# fancontroller.net
KiCad netlist of a schematic drawn in EAGLE
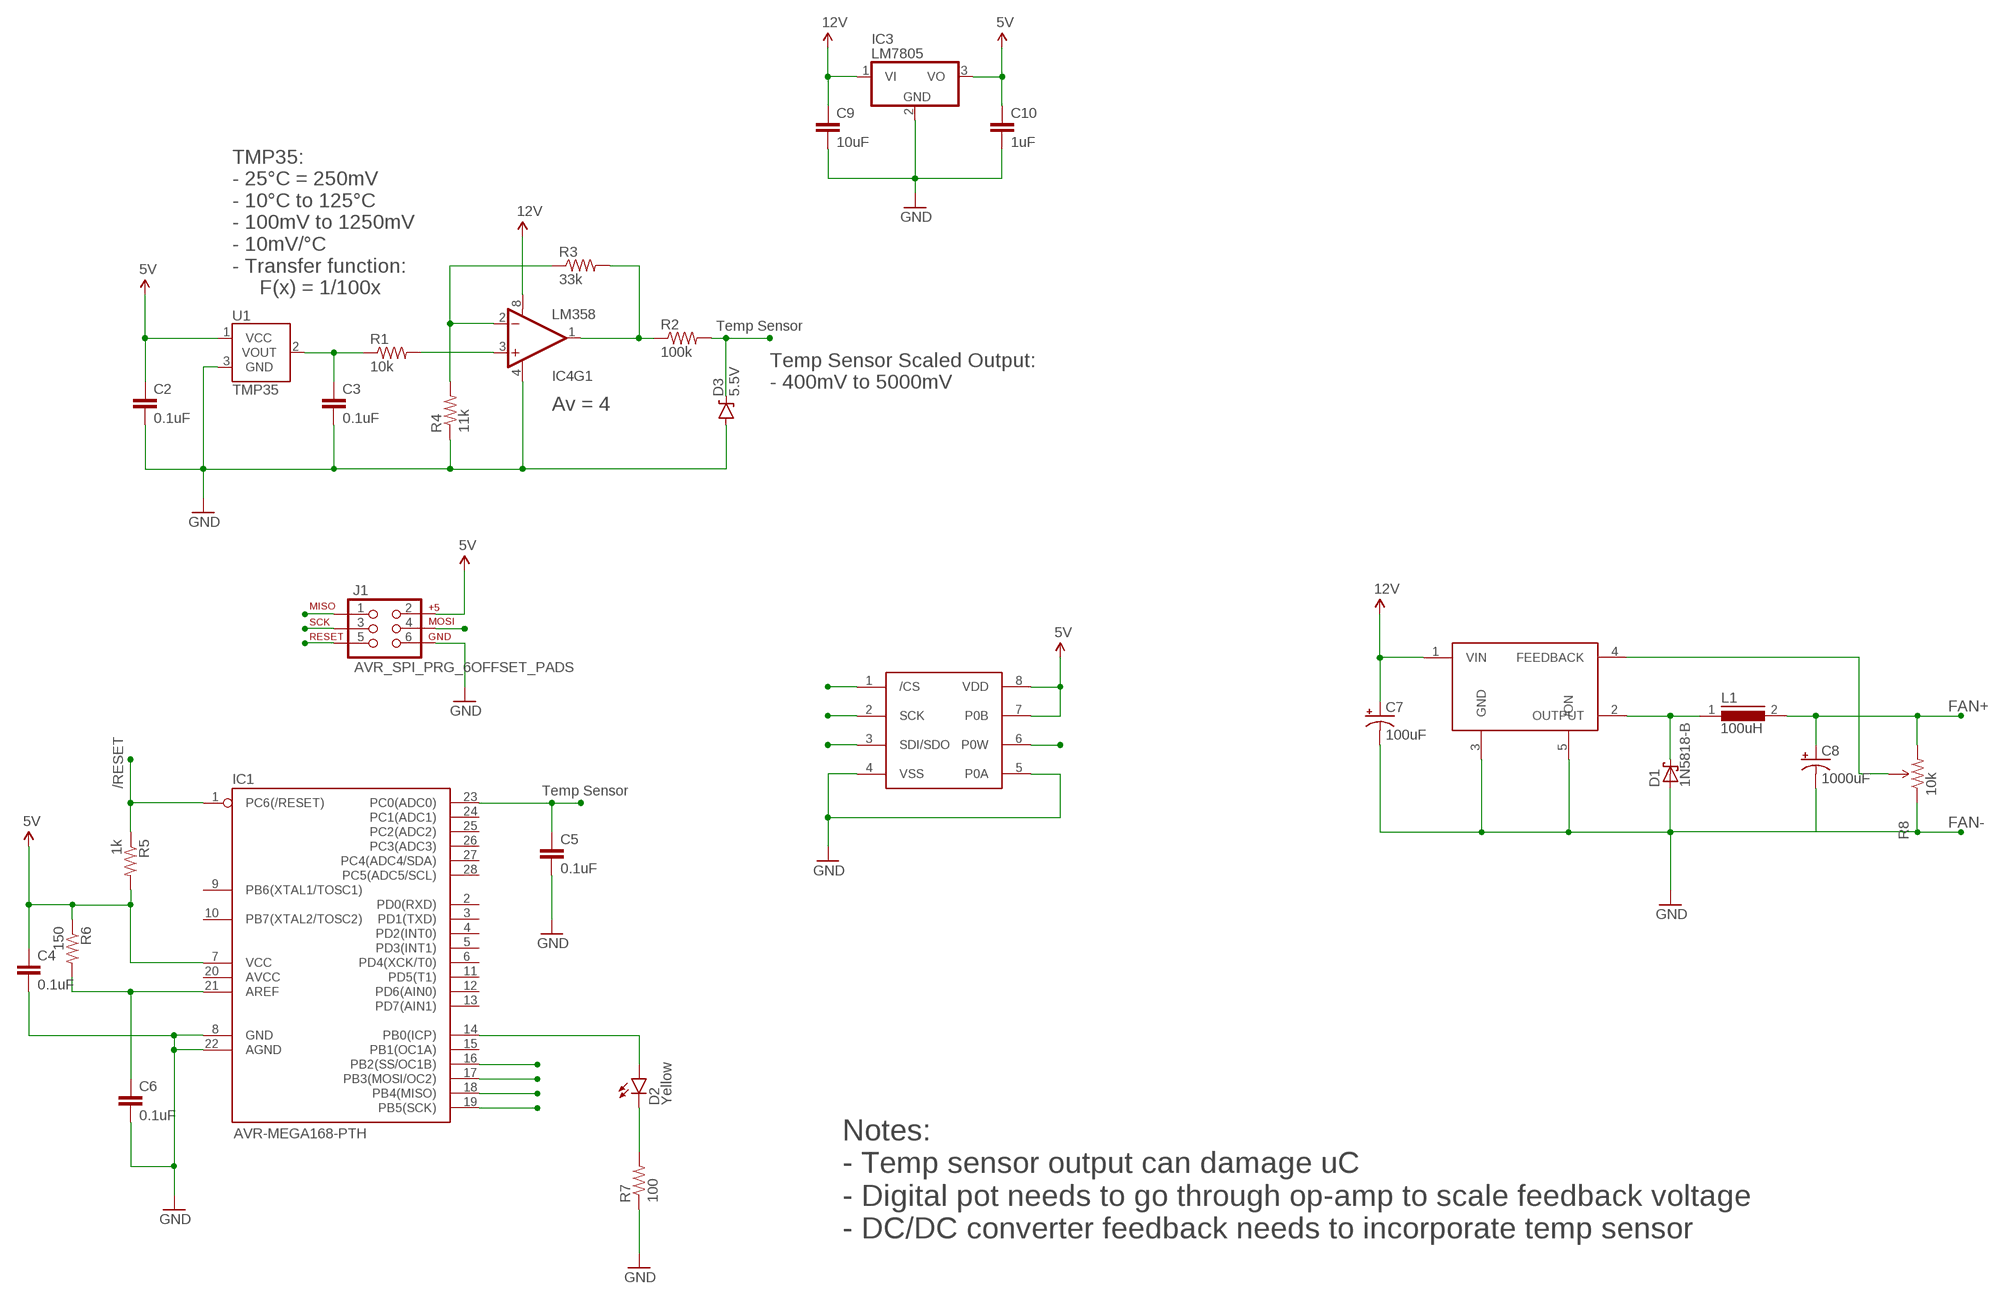
[diagram p0: schematic, sheet 1]

(export (version "E")
  (design (tool "Eeschema 10.0.6"))
  (components
    (comp (ref "C2")
      (value "0.1uF")
      (footprint "eagle-import:CAP-PTH-SMALL")
      (libsource (lib "eagle-import") (part "CAPPTH"))
    )
    (comp (ref "C3")
      (value "0.1uF")
      (footprint "eagle-import:CAP-PTH-SMALL")
      (libsource (lib "eagle-import") (part "CAPPTH"))
    )
    (comp (ref "C4")
      (value "0.1uF")
      (footprint "eagle-import:CAP-PTH-SMALL")
      (libsource (lib "eagle-import") (part "CAPPTH"))
    )
    (comp (ref "C5")
      (value "0.1uF")
      (footprint "eagle-import:CAP-PTH-SMALL")
      (libsource (lib "eagle-import") (part "CAPPTH"))
    )
    (comp (ref "C6")
      (value "0.1uF")
      (footprint "eagle-import:CAP-PTH-SMALL")
      (libsource (lib "eagle-import") (part "CAPPTH"))
    )
    (comp (ref "C7")
      (value "100uF")
      (footprint "eagle-import:CPOL-RADIAL-100UF-25V")
      (libsource (lib "eagle-import") (part "CAP_POLPTH1"))
    )
    (comp (ref "C8")
      (value "1000uF")
      (footprint "eagle-import:CPOL-RADIAL-100UF-25V")
      (libsource (lib "eagle-import") (part "CAP_POLPTH1"))
    )
    (comp (ref "C9")
      (value "10uF")
      (footprint "eagle-import:CAP-PTH-SMALL")
      (libsource (lib "eagle-import") (part "CAPPTH"))
    )
    (comp (ref "C10")
      (value "1uF")
      (footprint "eagle-import:CAP-PTH-SMALL")
      (libsource (lib "eagle-import") (part "CAPPTH"))
    )
    (comp (ref "D1")
      (value "1N5818-B")
      (footprint "eagle-import:DO41-7.6")
      (libsource (lib "eagle-import") (part "1N5818-B"))
    )
    (comp (ref "D2")
      (value "Yellow")
      (footprint "eagle-import:LED5MM")
      (libsource (lib "eagle-import") (part "LED5MM"))
    )
    (comp (ref "D3")
      (value "5.5V")
      (footprint "eagle-import:DIODE-ZENER")
      (libsource (lib "eagle-import") (part "DIODE-ZENERPTH"))
    )
    (comp (ref "IC1")
      (value "AVR-MEGA168-PTH")
      (footprint "eagle-import:DIL28-3")
      (libsource (lib "eagle-import") (part "AVR-MEGA8-PPTH"))
    )
    (comp (ref "IC3")
      (value "LM7805")
      (footprint "eagle-import:TO220V")
      (libsource (lib "eagle-import") (part "78TV12"))
    )
    (comp (ref "IC4")
      (value "LM358")
      (footprint "eagle-import:DIP08-KIT")
      (libsource (lib "eagle-import") (part "LM358KIT"))
    )
    (comp (ref "J1")
      (value "AVR_SPI_PRG_6OFFSET_PADS")
      (footprint "eagle-import:2X3_OFFSET")
      (libsource (lib "eagle-import") (part "AVR_SPI_PRG_6OFFSET_PADS"))
    )
    (comp (ref "L1")
      (value "100uH")
      (footprint "eagle-import:A26GFC")
      (libsource (lib "eagle-import") (part "A26GFC"))
    )
    (comp (ref "R1")
      (value "10k")
      (footprint "eagle-import:AXIAL-0.1")
      (libsource (lib "eagle-import") (part "10KOHM-1/4W-1%(PTH)VERT"))
    )
    (comp (ref "R2")
      (value "100k")
      (footprint "eagle-import:AXIAL-0.1")
      (libsource (lib "eagle-import") (part "10KOHM-1/4W-1%(PTH)VERT"))
    )
    (comp (ref "R3")
      (value "33k")
      (footprint "eagle-import:AXIAL-0.1")
      (libsource (lib "eagle-import") (part "10KOHM-1/4W-1%(PTH)VERT"))
    )
    (comp (ref "R4")
      (value "11k")
      (footprint "eagle-import:AXIAL-0.1")
      (libsource (lib "eagle-import") (part "10KOHM-1/4W-1%(PTH)VERT"))
    )
    (comp (ref "R5")
      (value "1k")
      (footprint "eagle-import:AXIAL-0.1")
      (libsource (lib "eagle-import") (part "10KOHM-1/4W-1%(PTH)VERT"))
    )
    (comp (ref "R6")
      (value "150")
      (footprint "eagle-import:AXIAL-0.1")
      (libsource (lib "eagle-import") (part "10KOHM-1/4W-1%(PTH)VERT"))
    )
    (comp (ref "R7")
      (value "100")
      (footprint "eagle-import:AXIAL-0.1")
      (libsource (lib "eagle-import") (part "10KOHM-1/4W-1%(PTH)VERT"))
    )
    (comp (ref "R8")
      (value "10k")
      (footprint "eagle-import:TRIM_POT_PTH")
      (libsource (lib "eagle-import") (part "TRIMPOTPTH"))
    )
    (comp (ref "U$1")
      (value "LM2576XXVERTICAL")
      (footprint "eagle-import:TO-220-5")
      (libsource (lib "eagle-import") (part "LM2576XXVERTICAL"))
    )
    (comp (ref "U$3")
      (value "MCP4131-103")
      (footprint "eagle-import:PDIP-8")
      (libsource (lib "eagle-import") (part "MCP41X1"))
    )
    (comp (ref "U1")
      (value "TMP35")
      (footprint "eagle-import:TO-92")
      (libsource (lib "eagle-import") (part "TMP36GT9"))
    )
  )
  (nets
    (net (code "1") (name "/MISO") (class "Default")
      (node (ref "IC1") (pin "18") (pinfunction "PB4(MISO)_18") (pintype "bidirectional"))
      (node (ref "J1") (pin "1") (pinfunction "1_1") (pintype "passive"))
    )
    (net (code "2") (name "/MOSI") (class "Default")
      (node (ref "IC1") (pin "17") (pinfunction "PB3(MOSI/OC2)_17") (pintype "bidirectional"))
      (node (ref "J1") (pin "4") (pinfunction "4_4") (pintype "passive"))
      (node (ref "U$3") (pin "3") (pinfunction "SDI/SDO_3") (pintype "bidirectional"))
    )
    (net (code "3") (name "/SCK") (class "Default")
      (node (ref "IC1") (pin "19") (pinfunction "PB5(SCK)_19") (pintype "bidirectional"))
      (node (ref "J1") (pin "3") (pinfunction "3_3") (pintype "passive"))
      (node (ref "U$3") (pin "2") (pinfunction "SCK_2") (pintype "bidirectional"))
    )
    (net (code "4") (name "/TEMP_SENSOR") (class "Default")
      (node (ref "C5") (pin "1") (pinfunction "1_1") (pintype "passive"))
      (node (ref "D3") (pin "P$1") (pinfunction "C_P$1") (pintype "passive"))
      (node (ref "IC1") (pin "23") (pinfunction "PC0(ADC0)_23") (pintype "bidirectional"))
      (node (ref "R2") (pin "P$2") (pinfunction "2_P$2") (pintype "passive"))
    )
    (net (code "5") (name "/{slash}RESET") (class "Default")
      (node (ref "IC1") (pin "1") (pinfunction "PC6(/RESET)_1") (pintype "bidirectional"))
      (node (ref "J1") (pin "5") (pinfunction "5_5") (pintype "passive"))
      (node (ref "R5") (pin "P$1") (pinfunction "1_P$1") (pintype "passive"))
    )
    (net (code "6") (name "/{slash}SS") (class "Default")
      (node (ref "IC1") (pin "16") (pinfunction "PB2(SS/OC1B)_16") (pintype "bidirectional"))
      (node (ref "U$3") (pin "1") (pinfunction "/CS_1") (pintype "bidirectional"))
    )
    (net (code "7") (name "5V") (class "Default")
      (node (ref "C10") (pin "1") (pinfunction "1_1") (pintype "passive"))
      (node (ref "C2") (pin "1") (pinfunction "1_1") (pintype "passive"))
      (node (ref "C4") (pin "1") (pinfunction "1_1") (pintype "passive"))
      (node (ref "IC1") (pin "7") (pinfunction "VCC_7") (pintype "bidirectional"))
      (node (ref "IC3") (pin "3") (pinfunction "VO_3") (pintype "passive"))
      (node (ref "J1") (pin "2") (pinfunction "2_2") (pintype "passive"))
      (node (ref "R5") (pin "P$2") (pinfunction "2_P$2") (pintype "passive"))
      (node (ref "R6") (pin "P$1") (pinfunction "1_P$1") (pintype "passive"))
      (node (ref "U$3") (pin "7") (pinfunction "P0B_7") (pintype "bidirectional"))
      (node (ref "U$3") (pin "8") (pinfunction "VDD_8") (pintype "bidirectional"))
      (node (ref "U1") (pin "1") (pinfunction "VCC_1") (pintype "bidirectional"))
    )
    (net (code "8") (name "12V") (class "Default")
      (node (ref "C7") (pin "1") (pinfunction "+_1") (pintype "passive"))
      (node (ref "C9") (pin "1") (pinfunction "1_1") (pintype "passive"))
      (node (ref "IC3") (pin "1") (pinfunction "VI_1") (pintype "input"))
      (node (ref "IC4") (pin "8") (pinfunction "V+_8") (pintype "power_in"))
      (node (ref "U$1") (pin "1") (pinfunction "VIN_1") (pintype "bidirectional"))
    )
    (net (code "9") (name "GND") (class "Default")
      (node (ref "C10") (pin "2") (pinfunction "2_2") (pintype "passive"))
      (node (ref "C2") (pin "2") (pinfunction "2_2") (pintype "passive"))
      (node (ref "C3") (pin "2") (pinfunction "2_2") (pintype "passive"))
      (node (ref "C4") (pin "2") (pinfunction "2_2") (pintype "passive"))
      (node (ref "C5") (pin "2") (pinfunction "2_2") (pintype "passive"))
      (node (ref "C6") (pin "2") (pinfunction "2_2") (pintype "passive"))
      (node (ref "C7") (pin "2") (pinfunction "-_2") (pintype "passive"))
      (node (ref "C8") (pin "2") (pinfunction "-_2") (pintype "passive"))
      (node (ref "C9") (pin "2") (pinfunction "2_2") (pintype "passive"))
      (node (ref "D1") (pin "A") (pinfunction "A_A") (pintype "passive"))
      (node (ref "D3") (pin "P$2") (pinfunction "A_P$2") (pintype "passive"))
      (node (ref "IC1") (pin "22") (pinfunction "AGND_22") (pintype "bidirectional"))
      (node (ref "IC1") (pin "8") (pinfunction "GND_8") (pintype "bidirectional"))
      (node (ref "IC3") (pin "2") (pinfunction "GND_2") (pintype "passive"))
      (node (ref "IC4") (pin "4") (pinfunction "V-_4") (pintype "power_in"))
      (node (ref "J1") (pin "6") (pinfunction "6_6") (pintype "passive"))
      (node (ref "R4") (pin "P$1") (pinfunction "1_P$1") (pintype "passive"))
      (node (ref "R7") (pin "P$1") (pinfunction "1_P$1") (pintype "passive"))
      (node (ref "R8") (pin "1") (pinfunction "CCW_1") (pintype "passive"))
      (node (ref "U$1") (pin "3") (pinfunction "GND_3") (pintype "bidirectional"))
      (node (ref "U$1") (pin "5") (pinfunction "/ON_5") (pintype "bidirectional"))
      (node (ref "U$3") (pin "4") (pinfunction "VSS_4") (pintype "bidirectional"))
      (node (ref "U$3") (pin "5") (pinfunction "P0A_5") (pintype "bidirectional"))
      (node (ref "U1") (pin "3") (pinfunction "GND_3") (pintype "bidirectional"))
    )
    (net (code "10") (name "Net-(C8-+)") (class "Default")
      (node (ref "C8") (pin "1") (pinfunction "+_1") (pintype "passive"))
      (node (ref "L1") (pin "2") (pinfunction "2_2") (pintype "passive"))
      (node (ref "R8") (pin "3") (pinfunction "CW_3") (pintype "passive"))
    )
    (net (code "11") (name "Net-(D2-C)") (class "Default")
      (node (ref "D2") (pin "K") (pinfunction "C_K") (pintype "passive"))
      (node (ref "R7") (pin "P$2") (pinfunction "2_P$2") (pintype "passive"))
    )
    (net (code "12") (name "Net-(IC1-AREF)") (class "Default")
      (node (ref "C6") (pin "1") (pinfunction "1_1") (pintype "passive"))
      (node (ref "IC1") (pin "21") (pinfunction "AREF_21") (pintype "bidirectional"))
      (node (ref "R6") (pin "P$2") (pinfunction "2_P$2") (pintype "passive"))
    )
    (net (code "13") (name "Net-(IC1-PB0(ICP))") (class "Default")
      (node (ref "D2") (pin "A") (pinfunction "A_A") (pintype "passive"))
      (node (ref "IC1") (pin "14") (pinfunction "PB0(ICP)_14") (pintype "bidirectional"))
    )
    (net (code "14") (name "Net-(IC4A-+IN)") (class "Default")
      (node (ref "IC4") (pin "3") (pinfunction "+IN_3") (pintype "input"))
      (node (ref "R1") (pin "P$2") (pinfunction "2_P$2") (pintype "passive"))
    )
    (net (code "15") (name "Net-(IC4A--IN)") (class "Default")
      (node (ref "IC4") (pin "2") (pinfunction "-IN_2") (pintype "input"))
      (node (ref "R3") (pin "P$1") (pinfunction "1_P$1") (pintype "passive"))
      (node (ref "R4") (pin "P$2") (pinfunction "2_P$2") (pintype "passive"))
    )
    (net (code "16") (name "Net-(IC4A-OUT)") (class "Default")
      (node (ref "IC4") (pin "1") (pinfunction "OUT_1") (pintype "output"))
      (node (ref "R2") (pin "P$1") (pinfunction "1_P$1") (pintype "passive"))
      (node (ref "R3") (pin "P$2") (pinfunction "2_P$2") (pintype "passive"))
    )
    (net (code "17") (name "Net-(R1-1)") (class "Default")
      (node (ref "C3") (pin "1") (pinfunction "1_1") (pintype "passive"))
      (node (ref "R1") (pin "P$1") (pinfunction "1_P$1") (pintype "passive"))
      (node (ref "U1") (pin "2") (pinfunction "VOUT_2") (pintype "bidirectional"))
    )
    (net (code "18") (name "Net-(R8-WIPER)") (class "Default")
      (node (ref "R8") (pin "2") (pinfunction "WIPER_2") (pintype "passive"))
      (node (ref "U$1") (pin "4") (pinfunction "FEEDBACK_4") (pintype "bidirectional"))
    )
    (net (code "19") (name "Net-(U$1-OUTPUT)") (class "Default")
      (node (ref "D1") (pin "C") (pinfunction "C_C") (pintype "passive"))
      (node (ref "L1") (pin "1") (pinfunction "1_1") (pintype "passive"))
      (node (ref "U$1") (pin "2") (pinfunction "OUTPUT_2") (pintype "bidirectional"))
    )
    (net (code "20") (name "unconnected-(IC1-AVCC-Pad20)") (class "Default")
      (node (ref "IC1") (pin "20") (pinfunction "AVCC_20") (pintype "bidirectional"))
    )
    (net (code "21") (name "unconnected-(IC1-PB1(OC1A)-Pad15)") (class "Default")
      (node (ref "IC1") (pin "15") (pinfunction "PB1(OC1A)_15") (pintype "bidirectional"))
    )
    (net (code "22") (name "unconnected-(IC1-PB6(XTAL1{slash}TOSC1)-Pad9)") (class "Default")
      (node (ref "IC1") (pin "9") (pinfunction "PB6(XTAL1/TOSC1)_9") (pintype "bidirectional"))
    )
    (net (code "23") (name "unconnected-(IC1-PB7(XTAL2{slash}TOSC2)-Pad10)") (class "Default")
      (node (ref "IC1") (pin "10") (pinfunction "PB7(XTAL2/TOSC2)_10") (pintype "bidirectional"))
    )
    (net (code "24") (name "unconnected-(IC1-PC1(ADC1)-Pad24)") (class "Default")
      (node (ref "IC1") (pin "24") (pinfunction "PC1(ADC1)_24") (pintype "bidirectional"))
    )
    (net (code "25") (name "unconnected-(IC1-PC2(ADC2)-Pad25)") (class "Default")
      (node (ref "IC1") (pin "25") (pinfunction "PC2(ADC2)_25") (pintype "bidirectional"))
    )
    (net (code "26") (name "unconnected-(IC1-PC3(ADC3)-Pad26)") (class "Default")
      (node (ref "IC1") (pin "26") (pinfunction "PC3(ADC3)_26") (pintype "bidirectional"))
    )
    (net (code "27") (name "unconnected-(IC1-PC4(ADC4{slash}SDA)-Pad27)") (class "Default")
      (node (ref "IC1") (pin "27") (pinfunction "PC4(ADC4/SDA)_27") (pintype "bidirectional"))
    )
    (net (code "28") (name "unconnected-(IC1-PC5(ADC5{slash}SCL)-Pad28)") (class "Default")
      (node (ref "IC1") (pin "28") (pinfunction "PC5(ADC5/SCL)_28") (pintype "bidirectional"))
    )
    (net (code "29") (name "unconnected-(IC1-PD0(RXD)-Pad2)") (class "Default")
      (node (ref "IC1") (pin "2") (pinfunction "PD0(RXD)_2") (pintype "bidirectional"))
    )
    (net (code "30") (name "unconnected-(IC1-PD1(TXD)-Pad3)") (class "Default")
      (node (ref "IC1") (pin "3") (pinfunction "PD1(TXD)_3") (pintype "bidirectional"))
    )
    (net (code "31") (name "unconnected-(IC1-PD2(INT0)-Pad4)") (class "Default")
      (node (ref "IC1") (pin "4") (pinfunction "PD2(INT0)_4") (pintype "bidirectional"))
    )
    (net (code "32") (name "unconnected-(IC1-PD3(INT1)-Pad5)") (class "Default")
      (node (ref "IC1") (pin "5") (pinfunction "PD3(INT1)_5") (pintype "bidirectional"))
    )
    (net (code "33") (name "unconnected-(IC1-PD4(XCK{slash}T0)-Pad6)") (class "Default")
      (node (ref "IC1") (pin "6") (pinfunction "PD4(XCK/T0)_6") (pintype "bidirectional"))
    )
    (net (code "34") (name "unconnected-(IC1-PD5(T1)-Pad11)") (class "Default")
      (node (ref "IC1") (pin "11") (pinfunction "PD5(T1)_11") (pintype "bidirectional"))
    )
    (net (code "35") (name "unconnected-(IC1-PD6(AIN0)-Pad12)") (class "Default")
      (node (ref "IC1") (pin "12") (pinfunction "PD6(AIN0)_12") (pintype "bidirectional"))
    )
    (net (code "36") (name "unconnected-(IC1-PD7(AIN1)-Pad13)") (class "Default")
      (node (ref "IC1") (pin "13") (pinfunction "PD7(AIN1)_13") (pintype "bidirectional"))
    )
    (net (code "37") (name "unconnected-(U$3-P0W-Pad6)") (class "Default")
      (node (ref "U$3") (pin "6") (pinfunction "P0W_6") (pintype "bidirectional"))
    )
  )
)
